# arduino_learning_cube.net
KiCad netlist of a schematic drawn in EasyEDA
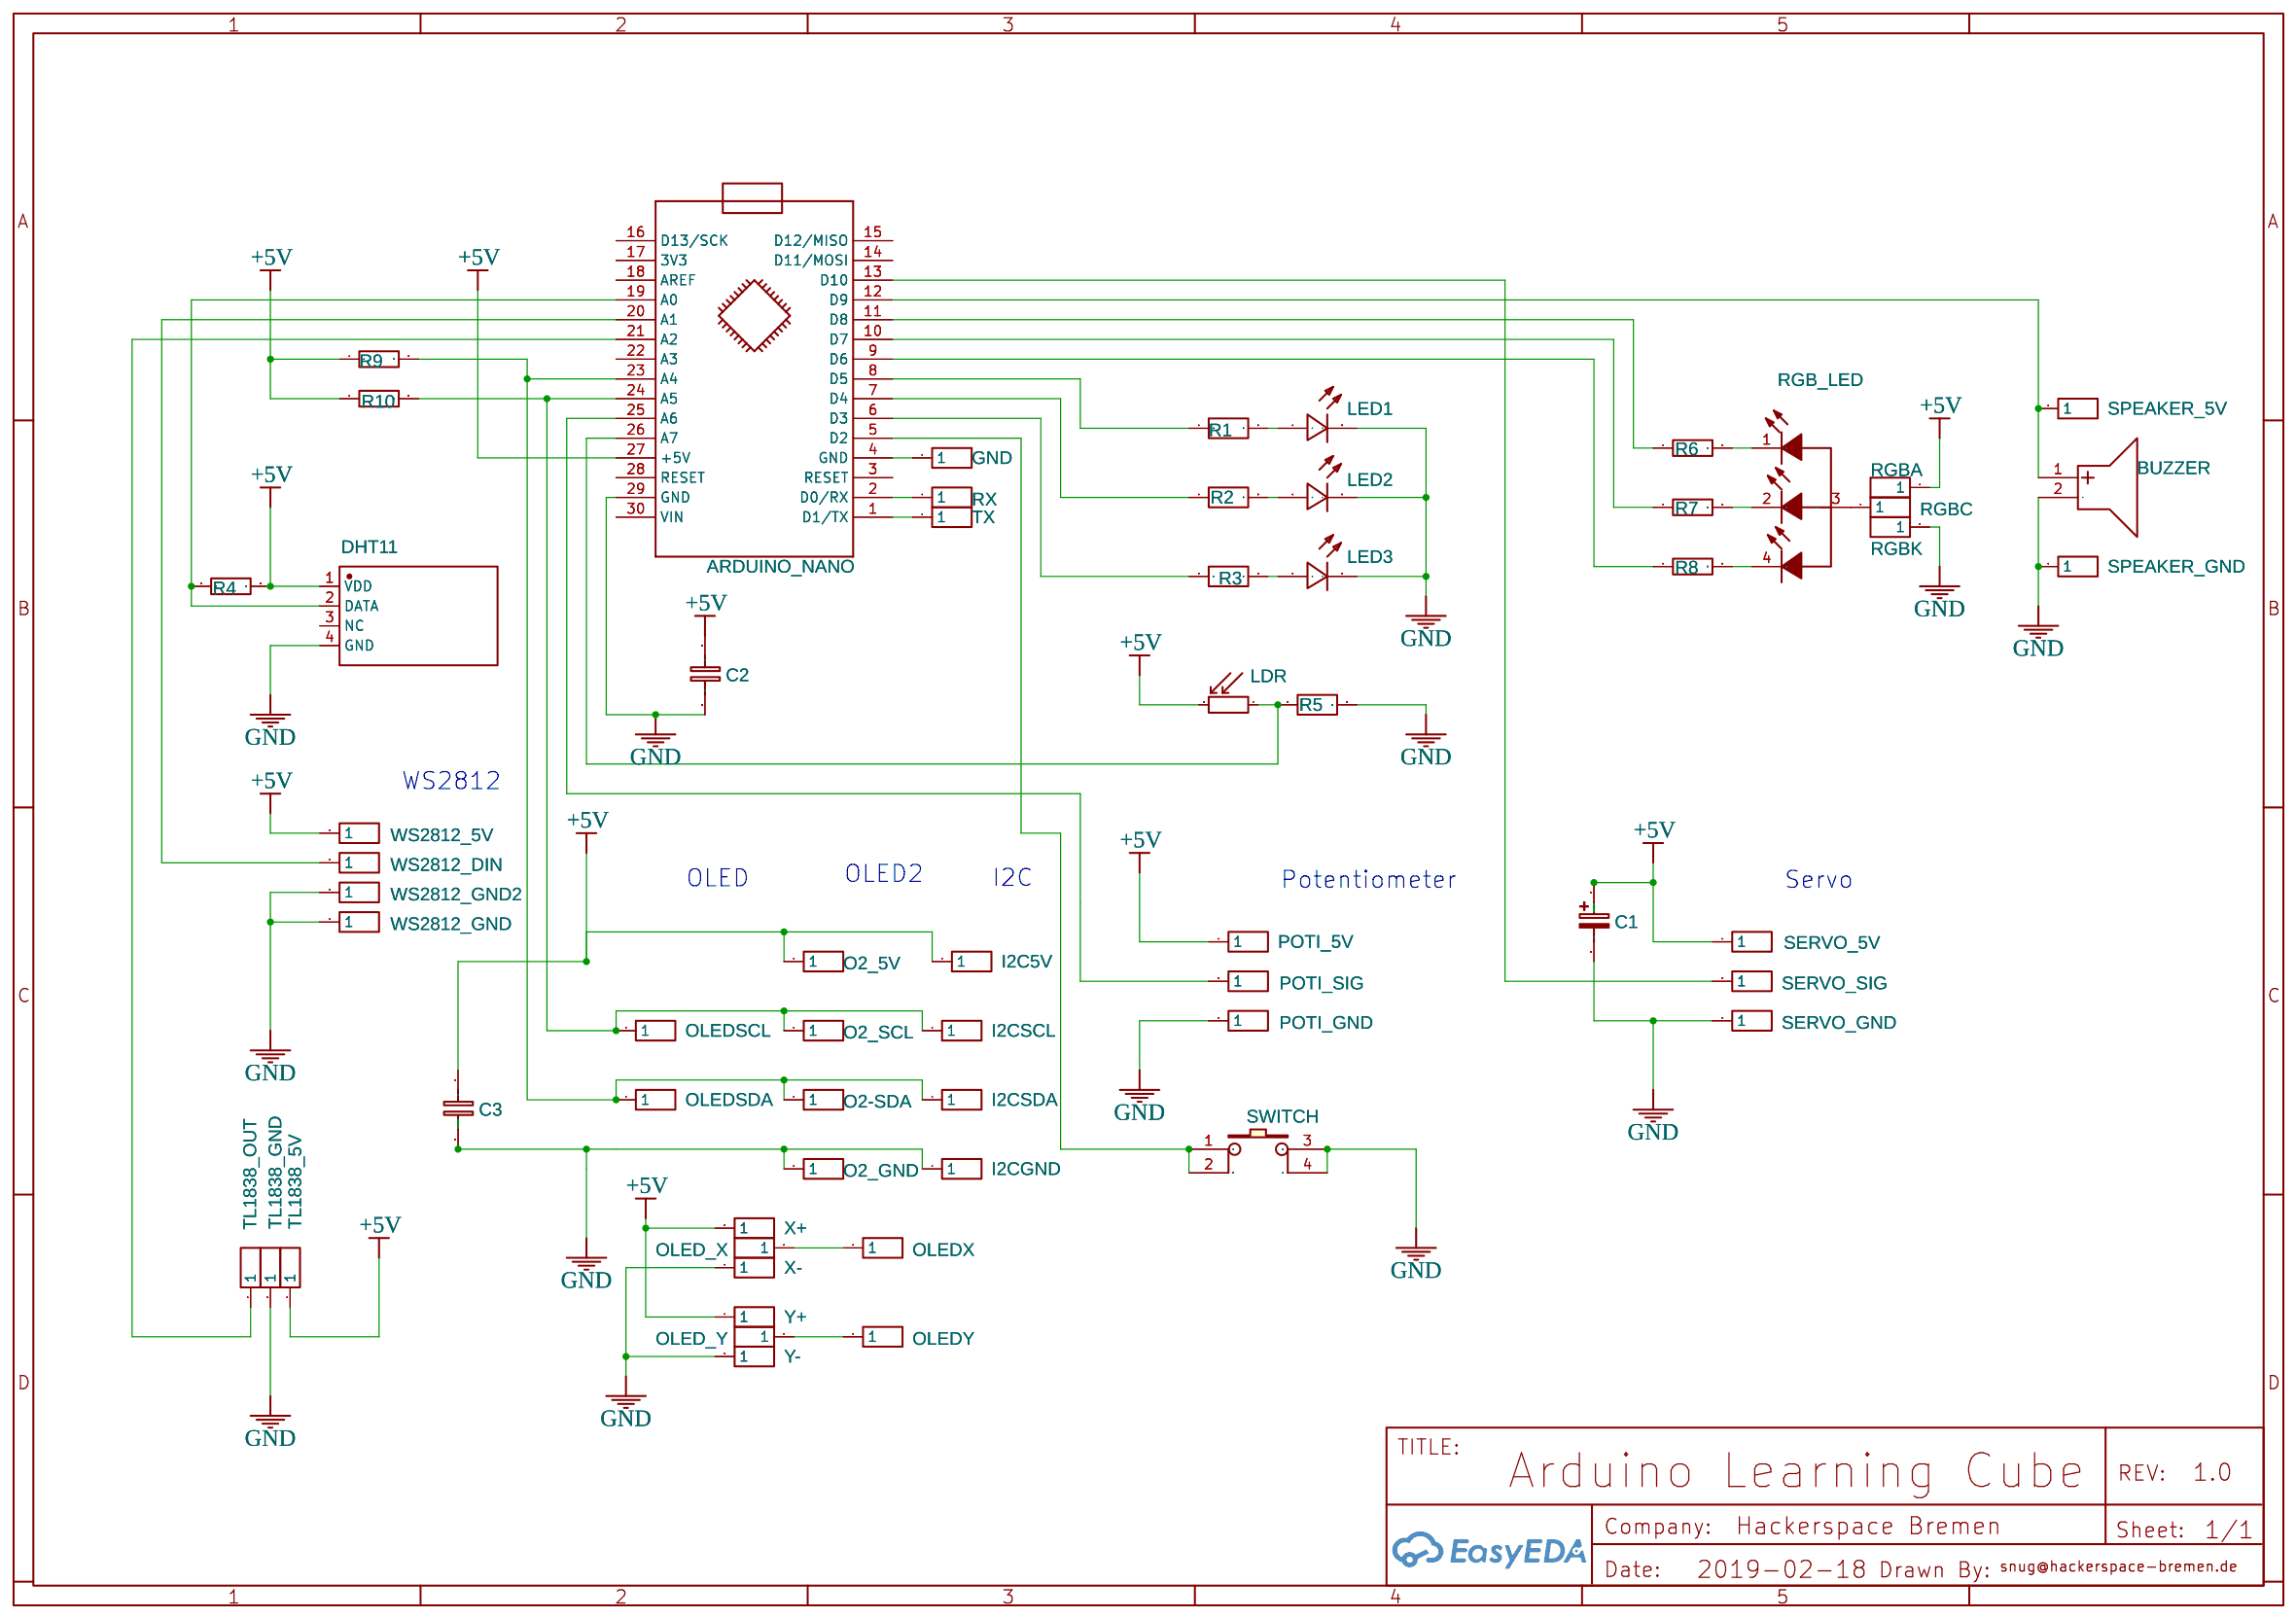
[diagram p0: schematic sheet]

(export (version "E")
  (design (tool "Eeschema 10.0.6"))
  (components
    (comp (ref "ARDUINO_NANO")
      (value "ARDUINO_NANO")
      (fields (field (name "BOM_Manufacturer Part") "?"))
      (libsource (lib "") (part "Unknown_375_180"))
    )
    (comp (ref "BUZZER")
      (value "ZL-DCY12075-2705P-7.6")
      (fields (field (name "BOM_Supplier Part") "C194535"))
      (libsource (lib "") (part "Unknown_1055_245"))
    )
    (comp (ref "C1")
      (value "1u")
      (fields (field (name "BOM_Manufacturer Part") "?"))
      (libsource (lib "") (part "Cap_Electrolytic(TH)_D8.0XF3.5_EU"))
    )
    (comp (ref "C2")
      (value "1u")
      (fields (field (name "BOM_Manufacturer Part") "?"))
      (libsource (lib "") (part "Cap_RAD-0.1_EU"))
    )
    (comp (ref "C3")
      (value "1u")
      (fields (field (name "BOM_Manufacturer Part") "?"))
      (libsource (lib "") (part "Cap_RAD-0.1_EU_1"))
    )
    (comp (ref "DHT11")
      (value "DHT11")
      (fields (field (name "BOM_Supplier Part") "C117051"))
      (libsource (lib "") (part "Unknown_200_305"))
    )
    (comp (ref "GND")
      (value "Header-Male-2.54_1x1")
      (fields (field (name "BOM_Supplier Part") "C81276"))
      (libsource (lib "") (part "Unknown_470_225"))
    )
    (comp (ref "I2C5V")
      (value "Header-Male-2.54_1x1")
      (fields (field (name "BOM_Supplier Part") "C81276"))
      (libsource (lib "") (part "Unknown_480_480"))
    )
    (comp (ref "I2CGND")
      (value "Header-Male-2.54_1x1")
      (fields (field (name "BOM_Supplier Part") "C81276"))
      (libsource (lib "") (part "Unknown_475_585"))
    )
    (comp (ref "I2CSCL")
      (value "Header-Male-2.54_1x1")
      (fields (field (name "BOM_Supplier Part") "C81276"))
      (libsource (lib "") (part "Unknown_475_515"))
    )
    (comp (ref "I2CSDA")
      (value "Header-Male-2.54_1x1")
      (fields (field (name "BOM_Supplier Part") "C81276"))
      (libsource (lib "") (part "Unknown_475_550"))
    )
    (comp (ref "LDR")
      (value "LDR07")
      (fields (field (name "BOM_Manufacturer Part") "?"))
      (libsource (lib "") (part "Unknown_625_350"))
    )
    (comp (ref "LED1")
      (value "LED-3MM")
      (fields
        (field (name "BOM_Manufacturer Part") "204-10SURD/S530-A3")
        (field (name "BOM_Supplier Part") "C99772")
      )
      (libsource (lib "") (part "Unknown_660_205"))
    )
    (comp (ref "LED2")
      (value "LED-3MM")
      (fields
        (field (name "BOM_Manufacturer Part") "204-10SURD/S530-A3")
        (field (name "BOM_Supplier Part") "C99772")
      )
      (libsource (lib "") (part "Unknown_660_240"))
    )
    (comp (ref "LED3")
      (value "LED-3MM")
      (fields
        (field (name "BOM_Manufacturer Part") "204-10SURD/S530-A3")
        (field (name "BOM_Supplier Part") "C99772")
      )
      (libsource (lib "") (part "Unknown_660_280"))
    )
    (comp (ref "O2-SDA")
      (value "Header-Male-2.54_1x1")
      (fields (field (name "BOM_Supplier Part") "C81276"))
      (libsource (lib "") (part "Unknown_405_550"))
    )
    (comp (ref "O2_5V")
      (value "Header-Male-2.54_1x1")
      (fields (field (name "BOM_Supplier Part") "C81276"))
      (libsource (lib "") (part "Unknown_405_480"))
    )
    (comp (ref "O2_GND")
      (value "Header-Male-2.54_1x1")
      (fields (field (name "BOM_Supplier Part") "C81276"))
      (libsource (lib "") (part "Unknown_405_585"))
    )
    (comp (ref "O2_SCL")
      (value "Header-Male-2.54_1x1")
      (fields (field (name "BOM_Supplier Part") "C81276"))
      (libsource (lib "") (part "Unknown_405_515"))
    )
    (comp (ref "OLEDSCL")
      (value "Header-Male-2.54_1x1")
      (fields (field (name "BOM_Supplier Part") "C81276"))
      (libsource (lib "") (part "Unknown_320_515"))
    )
    (comp (ref "OLEDSDA")
      (value "Header-Male-2.54_1x1")
      (fields (field (name "BOM_Supplier Part") "C81276"))
      (libsource (lib "") (part "Unknown_320_550"))
    )
    (comp (ref "OLEDX")
      (value "Header-Male-2.54_1x1")
      (fields (field (name "BOM_Supplier Part") "C81276"))
      (libsource (lib "") (part "Unknown_435_625"))
    )
    (comp (ref "OLEDY")
      (value "Header-Male-2.54_1x1")
      (fields (field (name "BOM_Supplier Part") "C81276"))
      (libsource (lib "") (part "Unknown_435_670"))
    )
    (comp (ref "OLED_X")
      (value "Header-Male-2.54_1x1")
      (fields (field (name "BOM_Supplier Part") "C81276"))
      (libsource (lib "") (part "Unknown_380_625"))
    )
    (comp (ref "OLED_Y")
      (value "Header-Male-2.54_1x1")
      (fields (field (name "BOM_Supplier Part") "C81276"))
      (libsource (lib "") (part "Unknown_380_670"))
    )
    (comp (ref "POTI_5V")
      (value "Header-Male-2.54_1x1")
      (fields (field (name "BOM_Supplier Part") "C81276"))
      (libsource (lib "") (part "Unknown_620_470"))
    )
    (comp (ref "POTI_GND")
      (value "Header-Male-2.54_1x1")
      (fields (field (name "BOM_Supplier Part") "C81276"))
      (libsource (lib "") (part "Unknown_620_510"))
    )
    (comp (ref "POTI_SIG")
      (value "Header-Male-2.54_1x1")
      (fields (field (name "BOM_Supplier Part") "C81276"))
      (libsource (lib "") (part "Unknown_620_490"))
    )
    (comp (ref "R1")
      (value "100")
      (fields (field (name "BOM_Manufacturer Part") "?"))
      (libsource (lib "") (part "Res_AXIAL-0.3(1/8W)_EU"))
    )
    (comp (ref "R2")
      (value "100")
      (fields (field (name "BOM_Manufacturer Part") "?"))
      (libsource (lib "") (part "Res_AXIAL-0.3(1/8W)_EU"))
    )
    (comp (ref "R3")
      (value "100")
      (fields (field (name "BOM_Manufacturer Part") "?"))
      (libsource (lib "") (part "Res_AXIAL-0.3(1/8W)_EU"))
    )
    (comp (ref "R4")
      (value "1k")
      (fields (field (name "BOM_Manufacturer Part") "?"))
      (libsource (lib "") (part "Res_AXIAL-0.3(1/8W)_EU_1"))
    )
    (comp (ref "R5")
      (value "1k")
      (fields (field (name "BOM_Manufacturer Part") "?"))
      (libsource (lib "") (part "Res_AXIAL-0.3(1/8W)_EU"))
    )
    (comp (ref "R6")
      (value "1k")
      (fields (field (name "BOM_Manufacturer Part") "?"))
      (libsource (lib "") (part "Res_AXIAL-0.3(1/8W)_EU_1"))
    )
    (comp (ref "R7")
      (value "1k")
      (fields (field (name "BOM_Manufacturer Part") "?"))
      (libsource (lib "") (part "Res_AXIAL-0.3(1/8W)_EU_1"))
    )
    (comp (ref "R8")
      (value "1k")
      (fields (field (name "BOM_Manufacturer Part") "?"))
      (libsource (lib "") (part "Res_AXIAL-0.3(1/8W)_EU_1"))
    )
    (comp (ref "R9")
      (value "1k")
      (fields (field (name "BOM_Manufacturer Part") "?"))
      (libsource (lib "") (part "Res_AXIAL-0.3(1/8W)_EU_1"))
    )
    (comp (ref "R10")
      (value "1k")
      (fields (field (name "BOM_Manufacturer Part") "?"))
      (libsource (lib "") (part "Res_AXIAL-0.3(1/8W)_EU_1"))
    )
    (comp (ref "RGBA")
      (value "Header-Male-2.54_1x1")
      (fields (field (name "BOM_Supplier Part") "C81276"))
      (libsource (lib "") (part "Unknown_955_240"))
    )
    (comp (ref "RGBC")
      (value "Header-Male-2.54_1x1")
      (fields (field (name "BOM_Supplier Part") "C81276"))
      (libsource (lib "") (part "Unknown_945_250"))
    )
    (comp (ref "RGBK")
      (value "Header-Male-2.54_1x1")
      (fields (field (name "BOM_Supplier Part") "C81276"))
      (libsource (lib "") (part "Unknown_955_260"))
    )
    (comp (ref "RGB_LED")
      (value "φ5 RGB Transparent")
      (fields
        (field (name "BOM_Manufacturer Part") "φ5 RGB Transparent LED")
        (field (name "BOM_Supplier Part") "C32985")
      )
      (libsource (lib "") (part "Unknown_905_245"))
    )
    (comp (ref "RX")
      (value "Header-Male-2.54_1x1")
      (fields (field (name "BOM_Supplier Part") "C81276"))
      (libsource (lib "") (part "Unknown_470_245"))
    )
    (comp (ref "SERVO_5V")
      (value "Header-Male-2.54_1x1")
      (fields (field (name "BOM_Supplier Part") "C81276"))
      (libsource (lib "") (part "Unknown_875_470"))
    )
    (comp (ref "SERVO_GND")
      (value "Header-Male-2.54_1x1")
      (fields (field (name "BOM_Supplier Part") "C81276"))
      (libsource (lib "") (part "Unknown_875_510"))
    )
    (comp (ref "SERVO_SIG")
      (value "Header-Male-2.54_1x1")
      (fields (field (name "BOM_Supplier Part") "C81276"))
      (libsource (lib "") (part "Unknown_875_490"))
    )
    (comp (ref "SPEAKER_5V")
      (value "Header-Male-2.54_1x1")
      (fields (field (name "BOM_Supplier Part") "C81276"))
      (libsource (lib "") (part "Unknown_1040_200"))
    )
    (comp (ref "SPEAKER_GND")
      (value "Header-Male-2.54_1x1")
      (fields (field (name "BOM_Supplier Part") "C81276"))
      (libsource (lib "") (part "Unknown_1040_280"))
    )
    (comp (ref "SWITCH")
      (value "SWITCH")
      (fields
        (field (name "BOM_Manufacturer Part") "K2-1102DP-K4SW-04")
        (field (name "BOM_Supplier Part") "C111992")
      )
      (libsource (lib "") (part "Unknown_635_585"))
    )
    (comp (ref "TL1838_5V")
      (value "Header-Male-2.54_1x1")
      (fields (field (name "BOM_Supplier Part") "C81276"))
      (libsource (lib "") (part "Unknown_140_640"))
    )
    (comp (ref "TL1838_GND")
      (value "Header-Male-2.54_1x1")
      (fields (field (name "BOM_Supplier Part") "C81276"))
      (libsource (lib "") (part "Unknown_130_640"))
    )
    (comp (ref "TL1838_OUT")
      (value "Header-Male-2.54_1x1")
      (fields (field (name "BOM_Supplier Part") "C81276"))
      (libsource (lib "") (part "Unknown_120_640"))
    )
    (comp (ref "TX")
      (value "Header-Male-2.54_1x1")
      (fields (field (name "BOM_Supplier Part") "C81276"))
      (libsource (lib "") (part "Unknown_470_255"))
    )
    (comp (ref "WS2812_5V")
      (value "Header-Male-2.54_1x1")
      (fields (field (name "BOM_Supplier Part") "C81276"))
      (libsource (lib "") (part "Unknown_170_415"))
    )
    (comp (ref "WS2812_DIN")
      (value "Header-Male-2.54_1x1")
      (fields (field (name "BOM_Supplier Part") "C81276"))
      (libsource (lib "") (part "Unknown_170_430"))
    )
    (comp (ref "WS2812_GND")
      (value "Header-Male-2.54_1x1")
      (fields (field (name "BOM_Supplier Part") "C81276"))
      (libsource (lib "") (part "Unknown_170_460"))
    )
    (comp (ref "WS2812_GND2")
      (value "Header-Male-2.54_1x1")
      (fields (field (name "BOM_Supplier Part") "C81276"))
      (libsource (lib "") (part "Unknown_170_445"))
    )
    (comp (ref "X+")
      (value "Header-Male-2.54_1x1")
      (fields (field (name "BOM_Supplier Part") "C81276"))
      (libsource (lib "") (part "Unknown_370_615"))
    )
    (comp (ref "X-")
      (value "Header-Male-2.54_1x1")
      (fields (field (name "BOM_Supplier Part") "C81276"))
      (libsource (lib "") (part "Unknown_370_635"))
    )
    (comp (ref "Y+")
      (value "Header-Male-2.54_1x1")
      (fields (field (name "BOM_Supplier Part") "C81276"))
      (libsource (lib "") (part "Unknown_370_660"))
    )
    (comp (ref "Y-")
      (value "Header-Male-2.54_1x1")
      (fields (field (name "BOM_Supplier Part") "C81276"))
      (libsource (lib "") (part "Unknown_370_680"))
    )
  )
  (nets
    (net (code "1") (name "+5V") (class "Default")
      (node (ref "ARDUINO_NANO") (pin "27") (pinfunction "+5V_27") (pintype "unspecified"))
      (node (ref "C1") (pin "1") (pinfunction "1_1") (pintype "unspecified"))
      (node (ref "C2") (pin "1") (pinfunction "1_1") (pintype "unspecified"))
      (node (ref "C3") (pin "1") (pinfunction "1_1") (pintype "unspecified"))
      (node (ref "DHT11") (pin "1") (pinfunction "VDD_1") (pintype "unspecified"))
      (node (ref "I2C5V") (pin "1") (pinfunction "1_1") (pintype "input"))
      (node (ref "LDR") (pin "2") (pintype "unspecified"))
      (node (ref "O2_5V") (pin "1") (pinfunction "1_1") (pintype "input"))
      (node (ref "POTI_5V") (pin "1") (pinfunction "1_1") (pintype "input"))
      (node (ref "R10") (pin "1") (pinfunction "1_1") (pintype "unspecified"))
      (node (ref "R4") (pin "2") (pinfunction "2_2") (pintype "unspecified"))
      (node (ref "R9") (pin "1") (pinfunction "1_1") (pintype "unspecified"))
      (node (ref "RGBA") (pin "1") (pinfunction "1_1") (pintype "input"))
      (node (ref "SERVO_5V") (pin "1") (pinfunction "1_1") (pintype "input"))
      (node (ref "TL1838_5V") (pin "1") (pinfunction "1_1") (pintype "input"))
      (node (ref "WS2812_5V") (pin "1") (pinfunction "1_1") (pintype "input"))
      (node (ref "X+") (pin "1") (pinfunction "1_1") (pintype "input"))
      (node (ref "Y+") (pin "1") (pinfunction "1_1") (pintype "input"))
    )
    (net (code "2") (name "GND") (class "Default")
      (node (ref "ARDUINO_NANO") (pin "29") (pinfunction "GND_29") (pintype "unspecified"))
      (node (ref "BUZZER") (pin "2") (pinfunction "-_2") (pintype "unspecified"))
      (node (ref "C1") (pin "2") (pinfunction "2_2") (pintype "unspecified"))
      (node (ref "C2") (pin "2") (pinfunction "2_2") (pintype "unspecified"))
      (node (ref "C3") (pin "2") (pinfunction "2_2") (pintype "unspecified"))
      (node (ref "DHT11") (pin "4") (pinfunction "GND_4") (pintype "unspecified"))
      (node (ref "I2CGND") (pin "1") (pinfunction "1_1") (pintype "input"))
      (node (ref "LED1") (pin "2") (pinfunction "-_2") (pintype "unspecified"))
      (node (ref "LED2") (pin "2") (pinfunction "-_2") (pintype "unspecified"))
      (node (ref "LED3") (pin "2") (pinfunction "-_2") (pintype "unspecified"))
      (node (ref "O2_GND") (pin "1") (pinfunction "1_1") (pintype "input"))
      (node (ref "POTI_GND") (pin "1") (pinfunction "1_1") (pintype "input"))
      (node (ref "R5") (pin "2") (pinfunction "2_2") (pintype "unspecified"))
      (node (ref "RGBK") (pin "1") (pinfunction "1_1") (pintype "input"))
      (node (ref "SERVO_GND") (pin "1") (pinfunction "1_1") (pintype "input"))
      (node (ref "SPEAKER_GND") (pin "1") (pinfunction "1_1") (pintype "input"))
      (node (ref "SWITCH") (pin "3") (pinfunction "3_3") (pintype "input"))
      (node (ref "SWITCH") (pin "4") (pinfunction "4_4") (pintype "input"))
      (node (ref "TL1838_GND") (pin "1") (pinfunction "1_1") (pintype "input"))
      (node (ref "WS2812_GND") (pin "1") (pinfunction "1_1") (pintype "input"))
      (node (ref "WS2812_GND2") (pin "1") (pinfunction "1_1") (pintype "input"))
      (node (ref "X-") (pin "1") (pinfunction "1_1") (pintype "input"))
      (node (ref "Y-") (pin "1") (pinfunction "1_1") (pintype "input"))
    )
    (net (code "3") (name "Net-(ARDUINO_NANO-A0)") (class "Default")
      (node (ref "ARDUINO_NANO") (pin "19") (pinfunction "A0_19") (pintype "unspecified"))
      (node (ref "DHT11") (pin "2") (pinfunction "DATA_2") (pintype "unspecified"))
      (node (ref "R4") (pin "1") (pinfunction "1_1") (pintype "unspecified"))
    )
    (net (code "4") (name "Net-(ARDUINO_NANO-A1)") (class "Default")
      (node (ref "ARDUINO_NANO") (pin "20") (pinfunction "A1_20") (pintype "unspecified"))
      (node (ref "WS2812_DIN") (pin "1") (pinfunction "1_1") (pintype "input"))
    )
    (net (code "5") (name "Net-(ARDUINO_NANO-A2)") (class "Default")
      (node (ref "ARDUINO_NANO") (pin "21") (pinfunction "A2_21") (pintype "unspecified"))
      (node (ref "TL1838_OUT") (pin "1") (pinfunction "1_1") (pintype "input"))
    )
    (net (code "6") (name "Net-(ARDUINO_NANO-A4)") (class "Default")
      (node (ref "ARDUINO_NANO") (pin "23") (pinfunction "A4_23") (pintype "unspecified"))
      (node (ref "I2CSDA") (pin "1") (pinfunction "1_1") (pintype "input"))
      (node (ref "O2-SDA") (pin "1") (pinfunction "1_1") (pintype "input"))
      (node (ref "OLEDSDA") (pin "1") (pinfunction "1_1") (pintype "input"))
      (node (ref "R9") (pin "2") (pinfunction "2_2") (pintype "unspecified"))
    )
    (net (code "7") (name "Net-(ARDUINO_NANO-A5)") (class "Default")
      (node (ref "ARDUINO_NANO") (pin "24") (pinfunction "A5_24") (pintype "unspecified"))
      (node (ref "I2CSCL") (pin "1") (pinfunction "1_1") (pintype "input"))
      (node (ref "O2_SCL") (pin "1") (pinfunction "1_1") (pintype "input"))
      (node (ref "OLEDSCL") (pin "1") (pinfunction "1_1") (pintype "input"))
      (node (ref "R10") (pin "2") (pinfunction "2_2") (pintype "unspecified"))
    )
    (net (code "8") (name "Net-(ARDUINO_NANO-A6)") (class "Default")
      (node (ref "ARDUINO_NANO") (pin "25") (pinfunction "A6_25") (pintype "unspecified"))
      (node (ref "POTI_SIG") (pin "1") (pinfunction "1_1") (pintype "input"))
    )
    (net (code "9") (name "Net-(ARDUINO_NANO-A7)") (class "Default")
      (node (ref "ARDUINO_NANO") (pin "26") (pinfunction "A7_26") (pintype "unspecified"))
      (node (ref "LDR") (pin "1") (pintype "unspecified"))
      (node (ref "R5") (pin "1") (pinfunction "1_1") (pintype "unspecified"))
    )
    (net (code "10") (name "Net-(ARDUINO_NANO-D0{slash}RX)") (class "Default")
      (node (ref "ARDUINO_NANO") (pin "2") (pinfunction "D0/RX_2") (pintype "unspecified"))
      (node (ref "RX") (pin "1") (pinfunction "1_1") (pintype "input"))
    )
    (net (code "11") (name "Net-(ARDUINO_NANO-D1{slash}TX)") (class "Default")
      (node (ref "ARDUINO_NANO") (pin "1") (pinfunction "D1/TX_1") (pintype "unspecified"))
      (node (ref "TX") (pin "1") (pinfunction "1_1") (pintype "input"))
    )
    (net (code "12") (name "Net-(ARDUINO_NANO-D2)") (class "Default")
      (node (ref "ARDUINO_NANO") (pin "5") (pinfunction "D2_5") (pintype "unspecified"))
      (node (ref "SWITCH") (pin "1") (pinfunction "1_1") (pintype "input"))
      (node (ref "SWITCH") (pin "2") (pinfunction "2_2") (pintype "input"))
    )
    (net (code "13") (name "Net-(ARDUINO_NANO-D3)") (class "Default")
      (node (ref "ARDUINO_NANO") (pin "6") (pinfunction "D3_6") (pintype "unspecified"))
      (node (ref "R3") (pin "1") (pinfunction "1_1") (pintype "unspecified"))
    )
    (net (code "14") (name "Net-(ARDUINO_NANO-D4)") (class "Default")
      (node (ref "ARDUINO_NANO") (pin "7") (pinfunction "D4_7") (pintype "unspecified"))
      (node (ref "R2") (pin "1") (pinfunction "1_1") (pintype "unspecified"))
    )
    (net (code "15") (name "Net-(ARDUINO_NANO-D5)") (class "Default")
      (node (ref "ARDUINO_NANO") (pin "8") (pinfunction "D5_8") (pintype "unspecified"))
      (node (ref "R1") (pin "1") (pinfunction "1_1") (pintype "unspecified"))
    )
    (net (code "16") (name "Net-(ARDUINO_NANO-D6)") (class "Default")
      (node (ref "ARDUINO_NANO") (pin "9") (pinfunction "D6_9") (pintype "unspecified"))
      (node (ref "R8") (pin "1") (pinfunction "1_1") (pintype "unspecified"))
    )
    (net (code "17") (name "Net-(ARDUINO_NANO-D7)") (class "Default")
      (node (ref "ARDUINO_NANO") (pin "10") (pinfunction "D7_10") (pintype "unspecified"))
      (node (ref "R7") (pin "1") (pinfunction "1_1") (pintype "unspecified"))
    )
    (net (code "18") (name "Net-(ARDUINO_NANO-D8)") (class "Default")
      (node (ref "ARDUINO_NANO") (pin "11") (pinfunction "D8_11") (pintype "unspecified"))
      (node (ref "R6") (pin "1") (pinfunction "1_1") (pintype "unspecified"))
    )
    (net (code "19") (name "Net-(ARDUINO_NANO-D9)") (class "Default")
      (node (ref "ARDUINO_NANO") (pin "12") (pinfunction "D9_12") (pintype "unspecified"))
      (node (ref "BUZZER") (pin "1") (pinfunction "+_1") (pintype "unspecified"))
      (node (ref "SPEAKER_5V") (pin "1") (pinfunction "1_1") (pintype "input"))
    )
    (net (code "20") (name "Net-(ARDUINO_NANO-D10)") (class "Default")
      (node (ref "ARDUINO_NANO") (pin "13") (pinfunction "D10_13") (pintype "unspecified"))
      (node (ref "SERVO_SIG") (pin "1") (pinfunction "1_1") (pintype "input"))
    )
    (net (code "21") (name "Net-(ARDUINO_NANO-GND-Pad4)") (class "Default")
      (node (ref "ARDUINO_NANO") (pin "4") (pinfunction "GND_4") (pintype "unspecified"))
      (node (ref "GND") (pin "1") (pinfunction "1_1") (pintype "input"))
    )
    (net (code "22") (name "Net-(LED1-+)") (class "Default")
      (node (ref "LED1") (pin "1") (pinfunction "+_1") (pintype "unspecified"))
      (node (ref "R1") (pin "2") (pinfunction "2_2") (pintype "unspecified"))
    )
    (net (code "23") (name "Net-(LED2-+)") (class "Default")
      (node (ref "LED2") (pin "1") (pinfunction "+_1") (pintype "unspecified"))
      (node (ref "R2") (pin "2") (pinfunction "2_2") (pintype "unspecified"))
    )
    (net (code "24") (name "Net-(LED3-+)") (class "Default")
      (node (ref "LED3") (pin "1") (pinfunction "+_1") (pintype "unspecified"))
      (node (ref "R3") (pin "2") (pinfunction "2_2") (pintype "unspecified"))
    )
    (net (code "25") (name "Net-(OLEDX-Pad1)") (class "Default")
      (node (ref "OLEDX") (pin "1") (pinfunction "1_1") (pintype "input"))
      (node (ref "OLED_X") (pin "1") (pinfunction "1_1") (pintype "input"))
    )
    (net (code "26") (name "Net-(OLEDY-Pad1)") (class "Default")
      (node (ref "OLEDY") (pin "1") (pinfunction "1_1") (pintype "input"))
      (node (ref "OLED_Y") (pin "1") (pinfunction "1_1") (pintype "input"))
    )
    (net (code "27") (name "Net-(R6-Pad2)") (class "Default")
      (node (ref "R6") (pin "2") (pinfunction "2_2") (pintype "unspecified"))
      (node (ref "RGB_LED") (pin "1") (pinfunction "K_1") (pintype "unspecified"))
    )
    (net (code "28") (name "Net-(R7-Pad2)") (class "Default")
      (node (ref "R7") (pin "2") (pinfunction "2_2") (pintype "unspecified"))
      (node (ref "RGB_LED") (pin "2") (pinfunction "K_2") (pintype "unspecified"))
    )
    (net (code "29") (name "Net-(R8-Pad2)") (class "Default")
      (node (ref "R8") (pin "2") (pinfunction "2_2") (pintype "unspecified"))
      (node (ref "RGB_LED") (pin "4") (pinfunction "K_4") (pintype "unspecified"))
    )
    (net (code "30") (name "Net-(RGB_LED-A)") (class "Default")
      (node (ref "RGBC") (pin "1") (pinfunction "1_1") (pintype "input"))
      (node (ref "RGB_LED") (pin "3") (pinfunction "A_3") (pintype "unspecified"))
    )
    (net (code "31") (name "unconnected-(ARDUINO_NANO-3V3-Pad17)") (class "Default")
      (node (ref "ARDUINO_NANO") (pin "17") (pinfunction "3V3_17") (pintype "unspecified"))
    )
    (net (code "32") (name "unconnected-(ARDUINO_NANO-A3-Pad22)") (class "Default")
      (node (ref "ARDUINO_NANO") (pin "22") (pinfunction "A3_22") (pintype "unspecified"))
    )
    (net (code "33") (name "unconnected-(ARDUINO_NANO-AREF-Pad18)") (class "Default")
      (node (ref "ARDUINO_NANO") (pin "18") (pinfunction "AREF_18") (pintype "unspecified"))
    )
    (net (code "34") (name "unconnected-(ARDUINO_NANO-D11{slash}MOSI-Pad14)") (class "Default")
      (node (ref "ARDUINO_NANO") (pin "14") (pinfunction "D11/MOSI_14") (pintype "unspecified"))
    )
    (net (code "35") (name "unconnected-(ARDUINO_NANO-D12{slash}MISO-Pad15)") (class "Default")
      (node (ref "ARDUINO_NANO") (pin "15") (pinfunction "D12/MISO_15") (pintype "unspecified"))
    )
    (net (code "36") (name "unconnected-(ARDUINO_NANO-D13{slash}SCK-Pad16)") (class "Default")
      (node (ref "ARDUINO_NANO") (pin "16") (pinfunction "D13/SCK_16") (pintype "unspecified"))
    )
    (net (code "37") (name "unconnected-(ARDUINO_NANO-RESET-Pad3)") (class "Default")
      (node (ref "ARDUINO_NANO") (pin "3") (pinfunction "RESET_3") (pintype "unspecified"))
    )
    (net (code "38") (name "unconnected-(ARDUINO_NANO-RESET-Pad28)") (class "Default")
      (node (ref "ARDUINO_NANO") (pin "28") (pinfunction "RESET_28") (pintype "unspecified"))
    )
    (net (code "39") (name "unconnected-(ARDUINO_NANO-VIN-Pad30)") (class "Default")
      (node (ref "ARDUINO_NANO") (pin "30") (pinfunction "VIN_30") (pintype "unspecified"))
    )
    (net (code "40") (name "unconnected-(DHT11-NC-Pad3)") (class "Default")
      (node (ref "DHT11") (pin "3") (pinfunction "NC_3") (pintype "unspecified"))
    )
  )
)
